# i2c_stm32.net
KiCad netlist of a schematic drawn in EAGLE
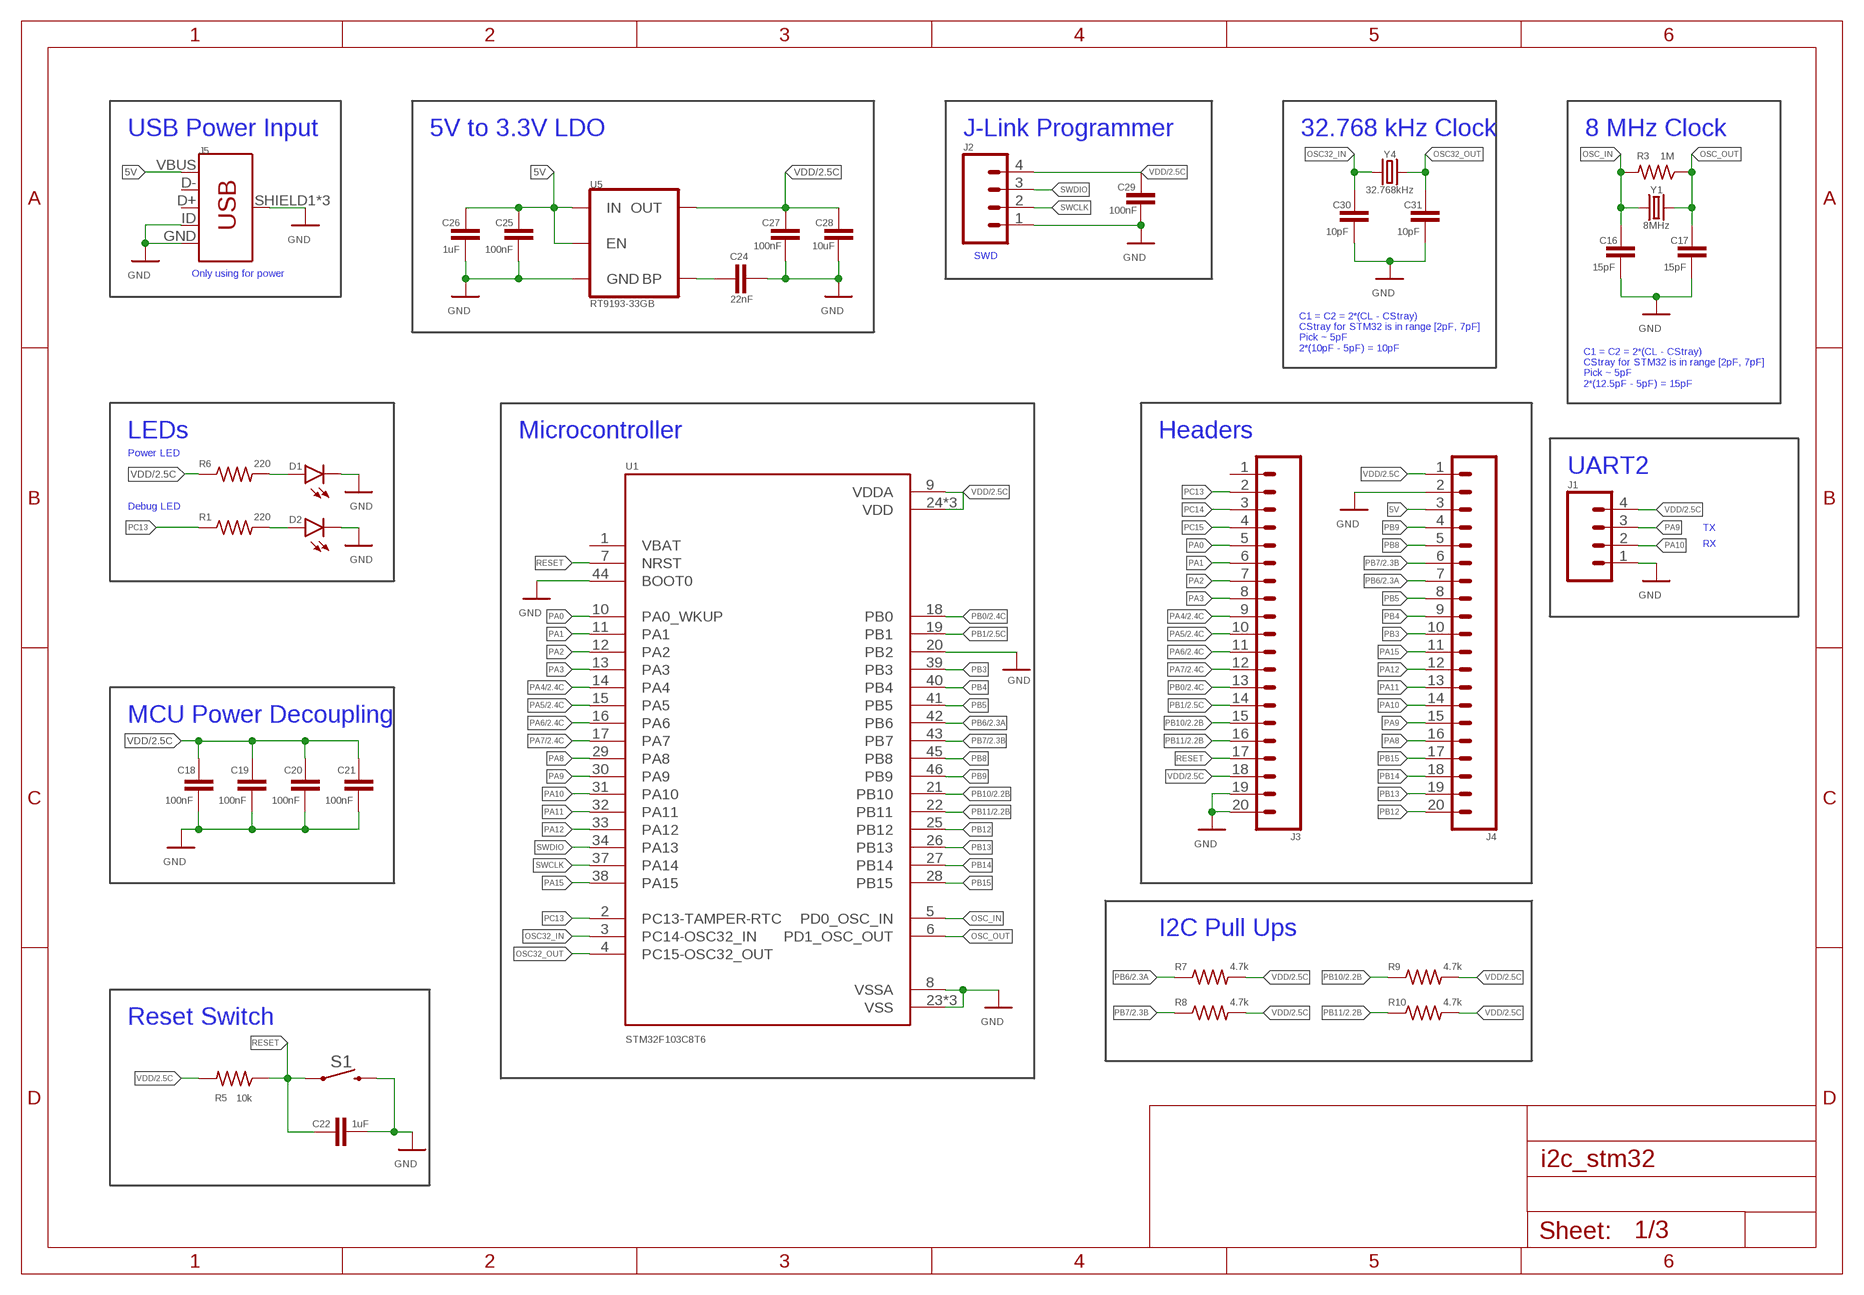
[diagram p0: schematic, sheet 1]
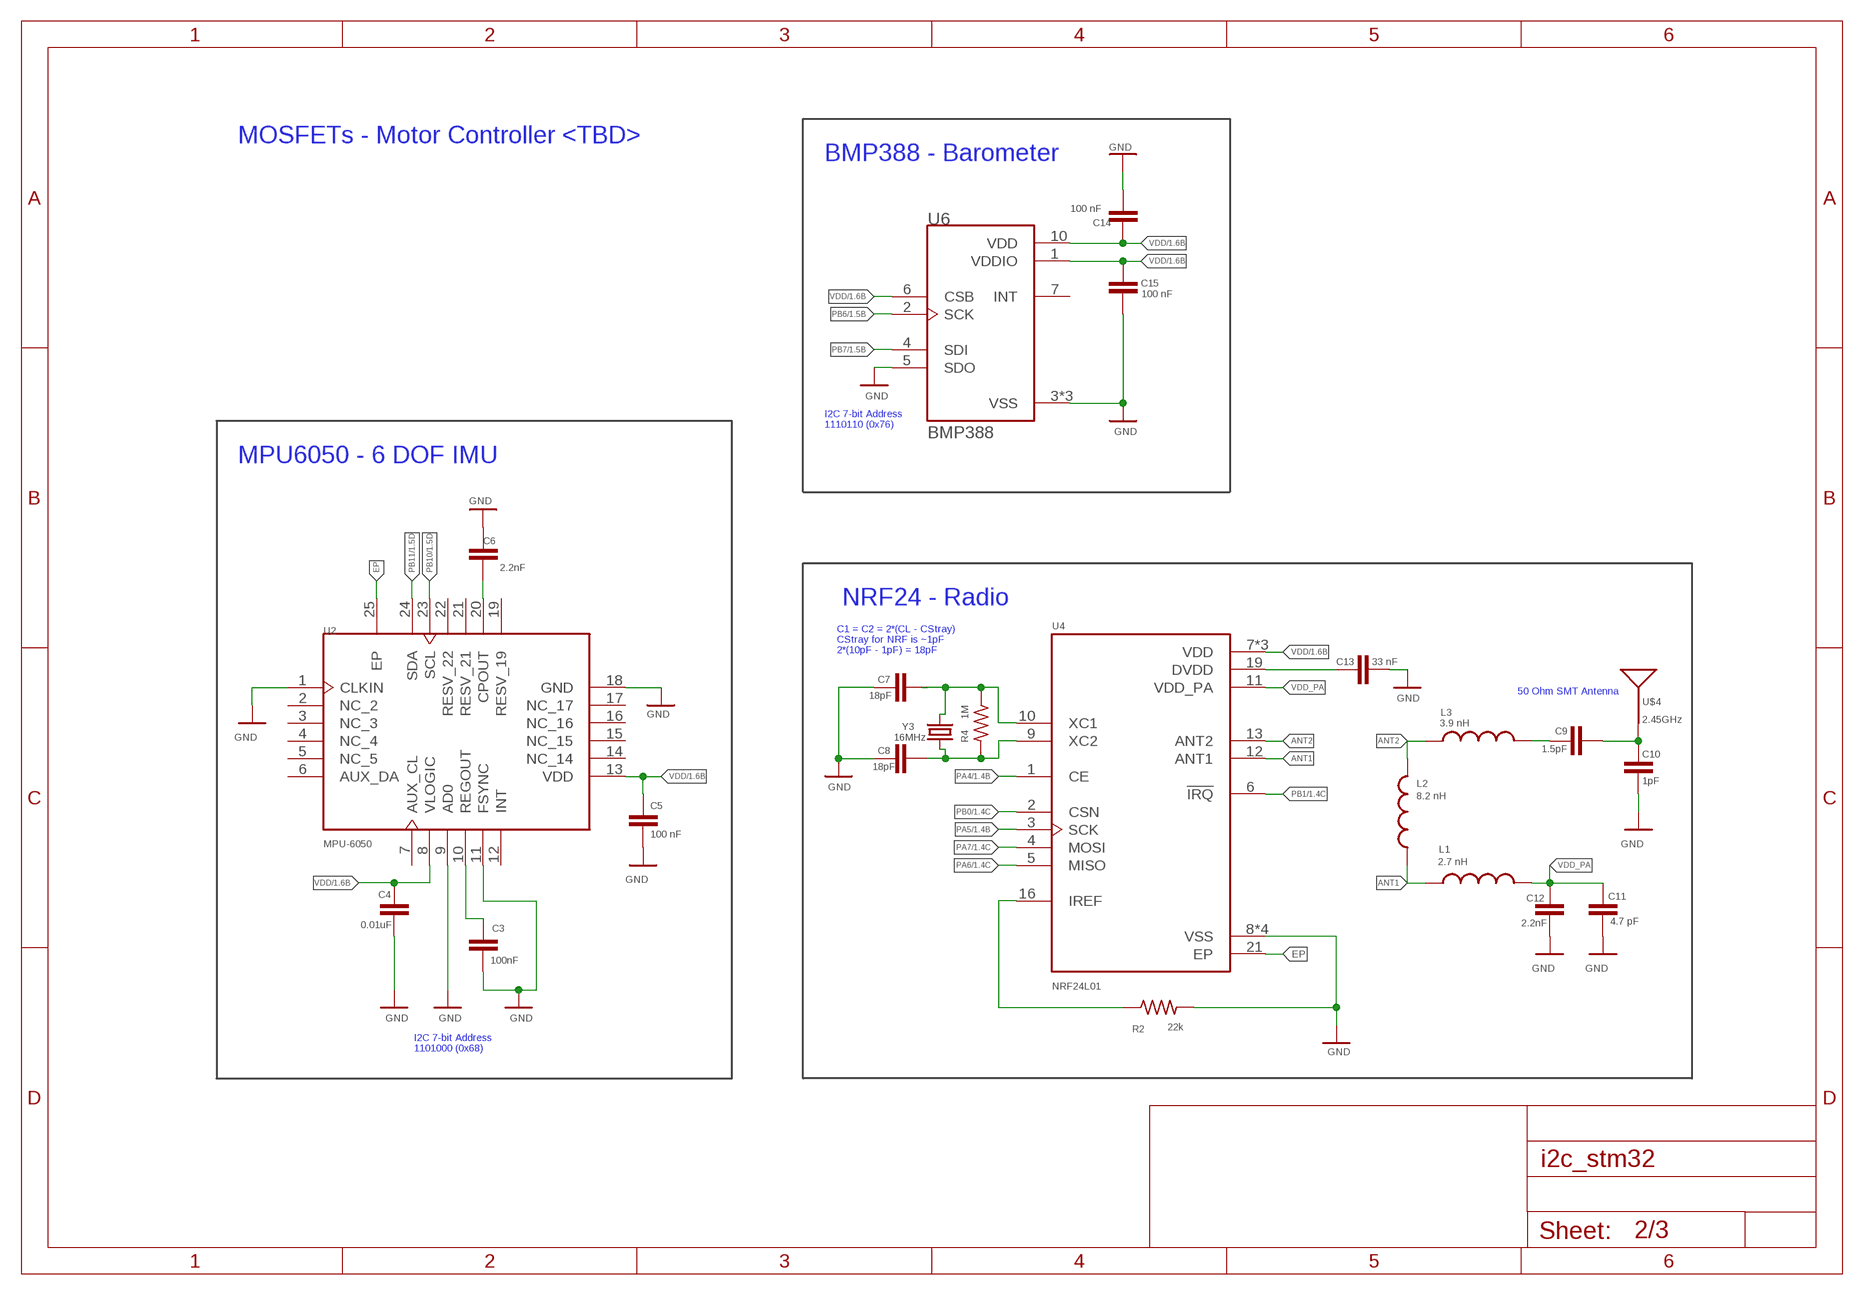
[diagram p1: schematic, sheet 2]
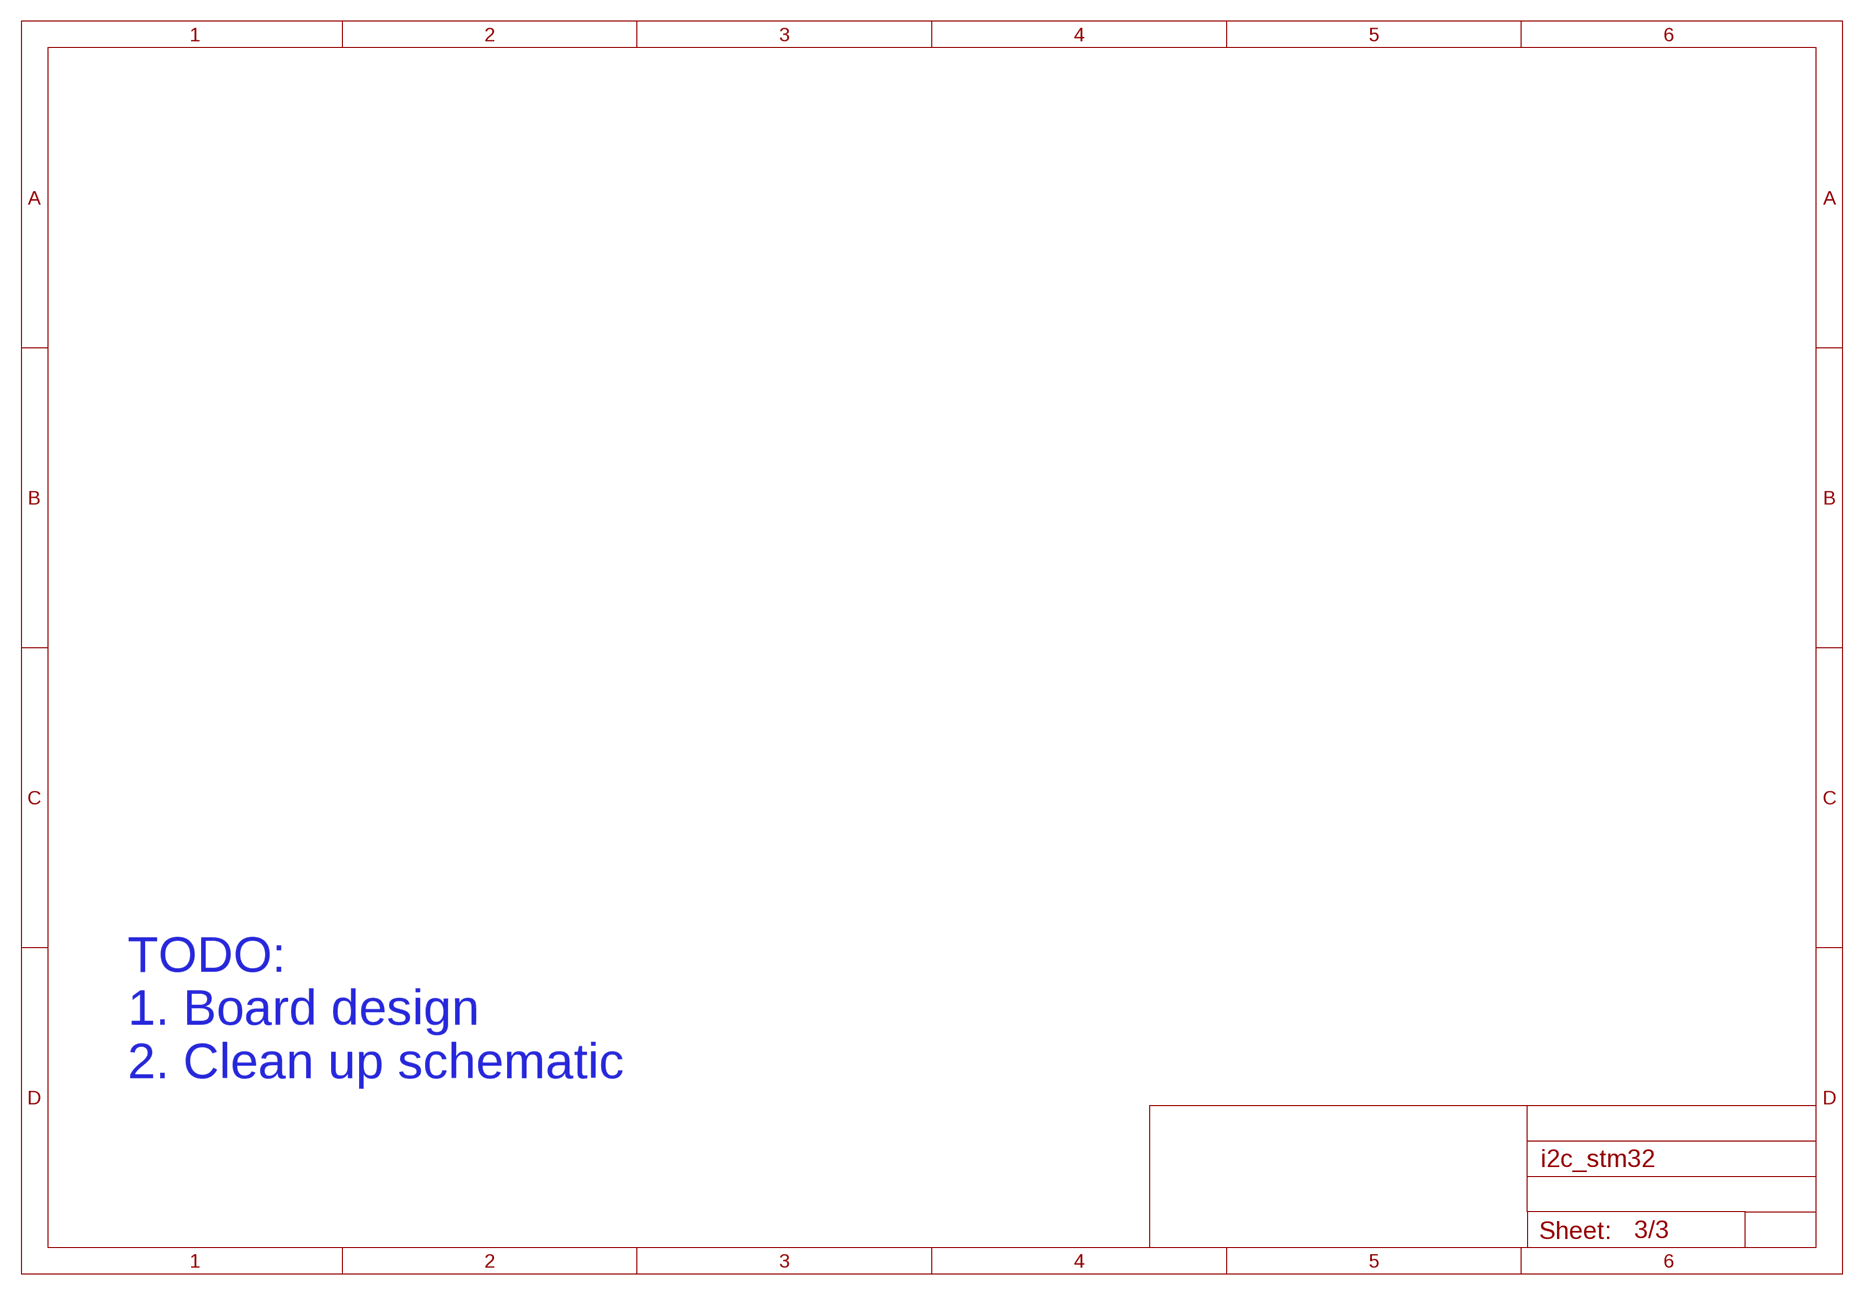
[diagram p2: schematic, sheet 3]

(export (version "E")
  (design (tool "Eeschema 10.0.6"))
  (components
    (comp (ref "C3")
      (value "100nF")
      (footprint "eagle-import:CAP_0603")
      (fields
        (field (name "DIGIKEY_PART_NUMBER") "399-7814-2-ND")
        (field (name "MANUFACTURER") "KEMET")
        (field (name "MPN") "C0603C100C5GACTU")
        (field (name "CREATED_BY") "PCBLayout.com")
      )
      (libsource (lib "eagle-import") (part "C0603C100C5GACTU"))
    )
    (comp (ref "C4")
      (value "0.01uF")
      (footprint "eagle-import:CAP_0603")
      (fields
        (field (name "DIGIKEY_PART_NUMBER") "399-7814-2-ND")
        (field (name "MANUFACTURER") "KEMET")
        (field (name "MPN") "C0603C100C5GACTU")
        (field (name "CREATED_BY") "PCBLayout.com")
      )
      (libsource (lib "eagle-import") (part "C0603C100C5GACTU"))
    )
    (comp (ref "C5")
      (value "100 nF")
      (footprint "eagle-import:CAP_0603")
      (fields
        (field (name "DIGIKEY_PART_NUMBER") "399-7814-2-ND")
        (field (name "MANUFACTURER") "KEMET")
        (field (name "MPN") "C0603C100C5GACTU")
        (field (name "CREATED_BY") "PCBLayout.com")
      )
      (libsource (lib "eagle-import") (part "C0603C100C5GACTU"))
    )
    (comp (ref "C6")
      (value "2.2nF")
      (footprint "eagle-import:CAP_0603")
      (fields
        (field (name "DIGIKEY_PART_NUMBER") "399-7814-2-ND")
        (field (name "MANUFACTURER") "KEMET")
        (field (name "MPN") "C0603C100C5GACTU")
        (field (name "CREATED_BY") "PCBLayout.com")
      )
      (libsource (lib "eagle-import") (part "C0603C100C5GACTU"))
    )
    (comp (ref "C7")
      (value "18pF")
      (footprint "eagle-import:CAP_0603")
      (fields
        (field (name "DIGIKEY_PART_NUMBER") "399-7814-2-ND")
        (field (name "MANUFACTURER") "KEMET")
        (field (name "MPN") "C0603C100C5GACTU")
        (field (name "CREATED_BY") "PCBLayout.com")
      )
      (libsource (lib "eagle-import") (part "C0603C100C5GACTU"))
    )
    (comp (ref "C8")
      (value "18pF")
      (footprint "eagle-import:CAP_0603")
      (fields
        (field (name "DIGIKEY_PART_NUMBER") "399-7814-2-ND")
        (field (name "MANUFACTURER") "KEMET")
        (field (name "MPN") "C0603C100C5GACTU")
        (field (name "CREATED_BY") "PCBLayout.com")
      )
      (libsource (lib "eagle-import") (part "C0603C100C5GACTU"))
    )
    (comp (ref "C9")
      (value "1.5pF")
      (footprint "eagle-import:CAP_0603")
      (fields
        (field (name "DIGIKEY_PART_NUMBER") "399-7814-2-ND")
        (field (name "MANUFACTURER") "KEMET")
        (field (name "MPN") "C0603C100C5GACTU")
        (field (name "CREATED_BY") "PCBLayout.com")
      )
      (libsource (lib "eagle-import") (part "C0603C100C5GACTU"))
    )
    (comp (ref "C10")
      (value "1pF")
      (footprint "eagle-import:CAP_0603")
      (fields
        (field (name "DIGIKEY_PART_NUMBER") "399-7814-2-ND")
        (field (name "MANUFACTURER") "KEMET")
        (field (name "MPN") "C0603C100C5GACTU")
        (field (name "CREATED_BY") "PCBLayout.com")
      )
      (libsource (lib "eagle-import") (part "C0603C100C5GACTU"))
    )
    (comp (ref "C11")
      (value "4.7 pF")
      (footprint "eagle-import:CAP_0603")
      (fields
        (field (name "DIGIKEY_PART_NUMBER") "399-7814-2-ND")
        (field (name "MANUFACTURER") "KEMET")
        (field (name "MPN") "C0603C100C5GACTU")
        (field (name "CREATED_BY") "PCBLayout.com")
      )
      (libsource (lib "eagle-import") (part "C0603C100C5GACTU"))
    )
    (comp (ref "C12")
      (value "2.2nF")
      (footprint "eagle-import:CAP_0603")
      (fields
        (field (name "DIGIKEY_PART_NUMBER") "399-7814-2-ND")
        (field (name "MANUFACTURER") "KEMET")
        (field (name "MPN") "C0603C100C5GACTU")
        (field (name "CREATED_BY") "PCBLayout.com")
      )
      (libsource (lib "eagle-import") (part "C0603C100C5GACTU"))
    )
    (comp (ref "C13")
      (value "33 nF")
      (footprint "eagle-import:CAP_0603")
      (fields
        (field (name "DIGIKEY_PART_NUMBER") "399-7814-2-ND")
        (field (name "MANUFACTURER") "KEMET")
        (field (name "MPN") "C0603C100C5GACTU")
        (field (name "CREATED_BY") "PCBLayout.com")
      )
      (libsource (lib "eagle-import") (part "C0603C100C5GACTU"))
    )
    (comp (ref "C14")
      (value "100 nF")
      (footprint "eagle-import:CAP_0603")
      (fields
        (field (name "DIGIKEY_PART_NUMBER") "399-7814-2-ND")
        (field (name "MANUFACTURER") "KEMET")
        (field (name "MPN") "C0603C100C5GACTU")
        (field (name "CREATED_BY") "PCBLayout.com")
      )
      (libsource (lib "eagle-import") (part "C0603C100C5GACTU"))
    )
    (comp (ref "C15")
      (value "100 nF")
      (footprint "eagle-import:CAP_0603")
      (fields
        (field (name "DIGIKEY_PART_NUMBER") "399-7814-2-ND")
        (field (name "MANUFACTURER") "KEMET")
        (field (name "MPN") "C0603C100C5GACTU")
        (field (name "CREATED_BY") "PCBLayout.com")
      )
      (libsource (lib "eagle-import") (part "C0603C100C5GACTU"))
    )
    (comp (ref "L1")
      (value "2.7 nH")
      (footprint "eagle-import:RESC0603_M")
      (libsource (lib "eagle-import") (part "INDUCTOR_0603_M"))
    )
    (comp (ref "L2")
      (value "8.2 nH")
      (footprint "eagle-import:RESC0603_M")
      (libsource (lib "eagle-import") (part "INDUCTOR_0603_M"))
    )
    (comp (ref "L3")
      (value "3.9 nH")
      (footprint "eagle-import:RESC0603_M")
      (libsource (lib "eagle-import") (part "INDUCTOR_0603_M"))
    )
    (comp (ref "R2")
      (value "22k")
      (footprint "eagle-import:RES_0603")
      (fields
        (field (name "DIGIKEY_PART_NUMBER") "311-0.0GRTR-ND")
        (field (name "MANUFACTURER") "Yageo")
        (field (name "MPN") "RC0603JR-070RL")
        (field (name "CREATED_BY") "PCBLayout.com")
      )
      (libsource (lib "eagle-import") (part "RC0603JR-070RL"))
    )
    (comp (ref "R4")
      (value "1M")
      (footprint "eagle-import:RES_0603")
      (fields
        (field (name "DIGIKEY_PART_NUMBER") "311-0.0GRTR-ND")
        (field (name "MANUFACTURER") "Yageo")
        (field (name "MPN") "RC0603JR-070RL")
        (field (name "CREATED_BY") "PCBLayout.com")
      )
      (libsource (lib "eagle-import") (part "RC0603JR-070RL"))
    )
    (comp (ref "U$4")
      (value "2.45GHz")
      (footprint "eagle-import:ANT-2.4GHZ-6.5X2.2MM")
      (libsource (lib "eagle-import") (part "ANTENNA2.4GHZ-6.5X2.2MM"))
    )
    (comp (ref "U2")
      (value "MPU-6050")
      (footprint "eagle-import:24-VFQFN")
      (fields
        (field (name "DIGIKEY_PART_NUMBER") "1428-1007-1-ND")
        (field (name "MANUFACTURER") "TDK InvenSense")
        (field (name "CREATED_BY") "PCBLayout.com")
      )
      (libsource (lib "eagle-import") (part "MPU-6050"))
    )
    (comp (ref "U4")
      (value "NRF24L01")
      (footprint "eagle-import:QFN50P400X400X95-21N")
      (fields (field (name "MF") "Nordic"))
      (libsource (lib "eagle-import") (part "NRF24L01"))
    )
    (comp (ref "U6")
      (value "BMP388")
      (footprint "eagle-import:PQFN50P200X200X80-10N")
      (fields (field (name "DIGI-KEY_PART_NUMBER") "828-1079-1-ND") (field (name "MF") "Bosch Sensortec"))
      (libsource (lib "eagle-import") (part "BMP388"))
    )
    (comp (ref "Y3")
      (value "16MHz")
      (footprint "eagle-import:CRYSTAL-SMD-5X3.2-4PAD")
      (libsource (lib "eagle-import") (part "CRYSTAL-16MHZSMD-5X3.2"))
    )
    (comp (ref "C16")
      (value "15pF")
      (footprint "eagle-import:CAP_0603")
      (fields
        (field (name "DIGIKEY_PART_NUMBER") "399-7814-2-ND")
        (field (name "MANUFACTURER") "KEMET")
        (field (name "MPN") "C0603C100C5GACTU")
        (field (name "CREATED_BY") "PCBLayout.com")
      )
      (libsource (lib "eagle-import") (part "C0603C100C5GACTU"))
    )
    (comp (ref "C17")
      (value "15pF")
      (footprint "eagle-import:CAP_0603")
      (fields
        (field (name "DIGIKEY_PART_NUMBER") "399-7814-2-ND")
        (field (name "MANUFACTURER") "KEMET")
        (field (name "MPN") "C0603C100C5GACTU")
        (field (name "CREATED_BY") "PCBLayout.com")
      )
      (libsource (lib "eagle-import") (part "C0603C100C5GACTU"))
    )
    (comp (ref "C18")
      (value "100nF")
      (footprint "eagle-import:CAP_0603")
      (fields
        (field (name "DIGIKEY_PART_NUMBER") "399-7814-2-ND")
        (field (name "MANUFACTURER") "KEMET")
        (field (name "MPN") "C0603C100C5GACTU")
        (field (name "CREATED_BY") "PCBLayout.com")
      )
      (libsource (lib "eagle-import") (part "C0603C100C5GACTU"))
    )
    (comp (ref "C19")
      (value "100nF")
      (footprint "eagle-import:CAP_0603")
      (fields
        (field (name "DIGIKEY_PART_NUMBER") "399-7814-2-ND")
        (field (name "MANUFACTURER") "KEMET")
        (field (name "MPN") "C0603C100C5GACTU")
        (field (name "CREATED_BY") "PCBLayout.com")
      )
      (libsource (lib "eagle-import") (part "C0603C100C5GACTU"))
    )
    (comp (ref "C20")
      (value "100nF")
      (footprint "eagle-import:CAP_0603")
      (fields
        (field (name "DIGIKEY_PART_NUMBER") "399-7814-2-ND")
        (field (name "MANUFACTURER") "KEMET")
        (field (name "MPN") "C0603C100C5GACTU")
        (field (name "CREATED_BY") "PCBLayout.com")
      )
      (libsource (lib "eagle-import") (part "C0603C100C5GACTU"))
    )
    (comp (ref "C21")
      (value "100nF")
      (footprint "eagle-import:CAP_0603")
      (fields
        (field (name "DIGIKEY_PART_NUMBER") "399-7814-2-ND")
        (field (name "MANUFACTURER") "KEMET")
        (field (name "MPN") "C0603C100C5GACTU")
        (field (name "CREATED_BY") "PCBLayout.com")
      )
      (libsource (lib "eagle-import") (part "C0603C100C5GACTU"))
    )
    (comp (ref "C22")
      (value "1uF")
      (footprint "eagle-import:CAP_0603")
      (fields
        (field (name "DIGIKEY_PART_NUMBER") "399-7814-2-ND")
        (field (name "MANUFACTURER") "KEMET")
        (field (name "MPN") "C0603C100C5GACTU")
        (field (name "CREATED_BY") "PCBLayout.com")
      )
      (libsource (lib "eagle-import") (part "C0603C100C5GACTU"))
    )
    (comp (ref "C24")
      (value "22nF")
      (footprint "eagle-import:CAP_0603")
      (fields
        (field (name "DIGIKEY_PART_NUMBER") "399-7814-2-ND")
        (field (name "MANUFACTURER") "KEMET")
        (field (name "MPN") "C0603C100C5GACTU")
        (field (name "CREATED_BY") "PCBLayout.com")
      )
      (libsource (lib "eagle-import") (part "C0603C100C5GACTU"))
    )
    (comp (ref "C25")
      (value "100nF")
      (footprint "eagle-import:CAP_0603")
      (fields
        (field (name "DIGIKEY_PART_NUMBER") "399-7814-2-ND")
        (field (name "MANUFACTURER") "KEMET")
        (field (name "MPN") "C0603C100C5GACTU")
        (field (name "CREATED_BY") "PCBLayout.com")
      )
      (libsource (lib "eagle-import") (part "C0603C100C5GACTU"))
    )
    (comp (ref "C26")
      (value "1uF")
      (footprint "eagle-import:CAP_0603")
      (fields
        (field (name "DIGIKEY_PART_NUMBER") "399-7814-2-ND")
        (field (name "MANUFACTURER") "KEMET")
        (field (name "MPN") "C0603C100C5GACTU")
        (field (name "CREATED_BY") "PCBLayout.com")
      )
      (libsource (lib "eagle-import") (part "C0603C100C5GACTU"))
    )
    (comp (ref "C27")
      (value "100nF")
      (footprint "eagle-import:CAP_0603")
      (fields
        (field (name "DIGIKEY_PART_NUMBER") "399-7814-2-ND")
        (field (name "MANUFACTURER") "KEMET")
        (field (name "MPN") "C0603C100C5GACTU")
        (field (name "CREATED_BY") "PCBLayout.com")
      )
      (libsource (lib "eagle-import") (part "C0603C100C5GACTU"))
    )
    (comp (ref "C28")
      (value "10uF")
      (footprint "eagle-import:CAP_0603")
      (fields
        (field (name "DIGIKEY_PART_NUMBER") "399-7814-2-ND")
        (field (name "MANUFACTURER") "KEMET")
        (field (name "MPN") "C0603C100C5GACTU")
        (field (name "CREATED_BY") "PCBLayout.com")
      )
      (libsource (lib "eagle-import") (part "C0603C100C5GACTU"))
    )
    (comp (ref "C29")
      (value "100nF")
      (footprint "eagle-import:CAP_0603")
      (fields
        (field (name "DIGIKEY_PART_NUMBER") "399-7814-2-ND")
        (field (name "MANUFACTURER") "KEMET")
        (field (name "MPN") "C0603C100C5GACTU")
        (field (name "CREATED_BY") "PCBLayout.com")
      )
      (libsource (lib "eagle-import") (part "C0603C100C5GACTU"))
    )
    (comp (ref "C30")
      (value "10pF")
      (footprint "eagle-import:CAP_0603")
      (fields
        (field (name "DIGIKEY_PART_NUMBER") "399-7814-2-ND")
        (field (name "MANUFACTURER") "KEMET")
        (field (name "MPN") "C0603C100C5GACTU")
        (field (name "CREATED_BY") "PCBLayout.com")
      )
      (libsource (lib "eagle-import") (part "C0603C100C5GACTU"))
    )
    (comp (ref "C31")
      (value "10pF")
      (footprint "eagle-import:CAP_0603")
      (fields
        (field (name "DIGIKEY_PART_NUMBER") "399-7814-2-ND")
        (field (name "MANUFACTURER") "KEMET")
        (field (name "MPN") "C0603C100C5GACTU")
        (field (name "CREATED_BY") "PCBLayout.com")
      )
      (libsource (lib "eagle-import") (part "C0603C100C5GACTU"))
    )
    (comp (ref "D1")
      (value "LED0603")
      (footprint "eagle-import:LED-0603")
      (libsource (lib "eagle-import") (part "LED0603"))
    )
    (comp (ref "D2")
      (value "LED0603")
      (footprint "eagle-import:LED-0603")
      (libsource (lib "eagle-import") (part "LED0603"))
    )
    (comp (ref "J1")
      (value "CONN_04")
      (footprint "eagle-import:1X04")
      (libsource (lib "eagle-import") (part "CONN_04"))
    )
    (comp (ref "J2")
      (value "CONN_04")
      (footprint "eagle-import:1X04")
      (libsource (lib "eagle-import") (part "CONN_04"))
    )
    (comp (ref "J3")
      (value "CONN_20")
      (footprint "eagle-import:1X20")
      (libsource (lib "eagle-import") (part "CONN_20"))
    )
    (comp (ref "J4")
      (value "CONN_20")
      (footprint "eagle-import:1X20")
      (libsource (lib "eagle-import") (part "CONN_20"))
    )
    (comp (ref "J5")
      (value "USB_MICRO-B_FEMALE-SMT")
      (footprint "eagle-import:USB-B-MICRO-SMD")
      (libsource (lib "eagle-import") (part "USB_MICRO-B_FEMALE-SMT"))
    )
    (comp (ref "R1")
      (value "220")
      (footprint "eagle-import:RES_0603")
      (fields
        (field (name "DIGIKEY_PART_NUMBER") "311-0.0GRTR-ND")
        (field (name "MANUFACTURER") "Yageo")
        (field (name "MPN") "RC0603JR-070RL")
        (field (name "CREATED_BY") "PCBLayout.com")
      )
      (libsource (lib "eagle-import") (part "RC0603JR-070RL"))
    )
    (comp (ref "R3")
      (value "1M")
      (footprint "eagle-import:RES_0603")
      (fields
        (field (name "DIGIKEY_PART_NUMBER") "311-0.0GRTR-ND")
        (field (name "MANUFACTURER") "Yageo")
        (field (name "MPN") "RC0603JR-070RL")
        (field (name "CREATED_BY") "PCBLayout.com")
      )
      (libsource (lib "eagle-import") (part "RC0603JR-070RL"))
    )
    (comp (ref "R5")
      (value "10k")
      (footprint "eagle-import:RES_0603")
      (fields
        (field (name "DIGIKEY_PART_NUMBER") "311-0.0GRTR-ND")
        (field (name "MANUFACTURER") "Yageo")
        (field (name "MPN") "RC0603JR-070RL")
        (field (name "CREATED_BY") "PCBLayout.com")
      )
      (libsource (lib "eagle-import") (part "RC0603JR-070RL"))
    )
    (comp (ref "R6")
      (value "220")
      (footprint "eagle-import:RES_0603")
      (fields
        (field (name "DIGIKEY_PART_NUMBER") "311-0.0GRTR-ND")
        (field (name "MANUFACTURER") "Yageo")
        (field (name "MPN") "RC0603JR-070RL")
        (field (name "CREATED_BY") "PCBLayout.com")
      )
      (libsource (lib "eagle-import") (part "RC0603JR-070RL"))
    )
    (comp (ref "R7")
      (value "4.7k")
      (footprint "eagle-import:RES_0603")
      (fields
        (field (name "DIGIKEY_PART_NUMBER") "311-0.0GRTR-ND")
        (field (name "MANUFACTURER") "Yageo")
        (field (name "MPN") "RC0603JR-070RL")
        (field (name "CREATED_BY") "PCBLayout.com")
      )
      (libsource (lib "eagle-import") (part "RC0603JR-070RL"))
    )
    (comp (ref "R8")
      (value "4.7k")
      (footprint "eagle-import:RES_0603")
      (fields
        (field (name "DIGIKEY_PART_NUMBER") "311-0.0GRTR-ND")
        (field (name "MANUFACTURER") "Yageo")
        (field (name "MPN") "RC0603JR-070RL")
        (field (name "CREATED_BY") "PCBLayout.com")
      )
      (libsource (lib "eagle-import") (part "RC0603JR-070RL"))
    )
    (comp (ref "R9")
      (value "4.7k")
      (footprint "eagle-import:RES_0603")
      (fields
        (field (name "DIGIKEY_PART_NUMBER") "311-0.0GRTR-ND")
        (field (name "MANUFACTURER") "Yageo")
        (field (name "MPN") "RC0603JR-070RL")
        (field (name "CREATED_BY") "PCBLayout.com")
      )
      (libsource (lib "eagle-import") (part "RC0603JR-070RL"))
    )
    (comp (ref "R10")
      (value "4.7k")
      (footprint "eagle-import:RES_0603")
      (fields
        (field (name "DIGIKEY_PART_NUMBER") "311-0.0GRTR-ND")
        (field (name "MANUFACTURER") "Yageo")
        (field (name "MPN") "RC0603JR-070RL")
        (field (name "CREATED_BY") "PCBLayout.com")
      )
      (libsource (lib "eagle-import") (part "RC0603JR-070RL"))
    )
    (comp (ref "S1")
      (value "MOMENTARY-SWITCH-SPST-PTH-6.0MM")
      (footprint "eagle-import:TACTILE_SWITCH_PTH_6.0MM")
      (libsource (lib "eagle-import") (part "MOMENTARY-SWITCH-SPST-PTH-6.0MM"))
    )
    (comp (ref "U1")
      (value "STM32F103C8T6")
      (footprint "eagle-import:QFP50P900X900X160-48N")
      (fields (field (name "MF") "STMicroelectronics") (field (name "SPICEPREFIX") "X"))
      (libsource (lib "eagle-import") (part "STM32F103C8T6"))
    )
    (comp (ref "U5")
      (value "RT9193-33GB")
      (footprint "eagle-import:SOT23-5")
      (libsource (lib "eagle-import") (part "V_REG_MIC5205ADJ"))
    )
    (comp (ref "Y1")
      (value "8MHz")
      (footprint "eagle-import:CRYSTAL-SMD-5X3.2-4PAD")
      (libsource (lib "eagle-import") (part "CRYSTAL-8MHZSMD-5X3.2"))
    )
    (comp (ref "Y4")
      (value "32.768kHz")
      (footprint "eagle-import:CRYSTAL-SMD-3.2X1.5MM")
      (libsource (lib "eagle-import") (part "CRYSTAL-32.768KHZSMD-3.2X1.5"))
    )
  )
  (nets
    (net (code "1") (name "5V") (class "Default")
      (node (ref "C25") (pin "2") (pinfunction "2_2") (pintype "passive"))
      (node (ref "C26") (pin "2") (pinfunction "2_2") (pintype "passive"))
      (node (ref "J4") (pin "3") (pinfunction "3_3") (pintype "passive"))
      (node (ref "J5") (pin "VBUS") (pinfunction "VBUS_VBUS") (pintype "power_in"))
      (node (ref "U5") (pin "1") (pinfunction "IN_1") (pintype "input"))
      (node (ref "U5") (pin "3") (pinfunction "EN_3") (pintype "input"))
    )
    (net (code "2") (name "ANT1") (class "Default")
      (node (ref "L1") (pin "1") (pinfunction "1_1") (pintype "passive"))
      (node (ref "L2") (pin "1") (pinfunction "1_1") (pintype "passive"))
      (node (ref "U4") (pin "12") (pinfunction "ANT1_12") (pintype "bidirectional"))
    )
    (net (code "3") (name "ANT2") (class "Default")
      (node (ref "L2") (pin "2") (pinfunction "2_2") (pintype "passive"))
      (node (ref "L3") (pin "1") (pinfunction "1_1") (pintype "passive"))
      (node (ref "U4") (pin "13") (pinfunction "ANT2_13") (pintype "bidirectional"))
    )
    (net (code "4") (name "EP") (class "Default")
      (node (ref "U2") (pin "25") (pinfunction "EP_25") (pintype "power_in"))
      (node (ref "U4") (pin "21") (pinfunction "EP_21") (pintype "power_in"))
    )
    (net (code "5") (name "GND") (class "Default")
      (node (ref "C10") (pin "1") (pinfunction "1_1") (pintype "passive"))
      (node (ref "C11") (pin "1") (pinfunction "1_1") (pintype "passive"))
      (node (ref "C12") (pin "1") (pinfunction "1_1") (pintype "passive"))
      (node (ref "C13") (pin "2") (pinfunction "2_2") (pintype "passive"))
      (node (ref "C14") (pin "2") (pinfunction "2_2") (pintype "passive"))
      (node (ref "C15") (pin "1") (pinfunction "1_1") (pintype "passive"))
      (node (ref "C16") (pin "2") (pinfunction "2_2") (pintype "passive"))
      (node (ref "C17") (pin "2") (pinfunction "2_2") (pintype "passive"))
      (node (ref "C18") (pin "2") (pinfunction "2_2") (pintype "passive"))
      (node (ref "C19") (pin "2") (pinfunction "2_2") (pintype "passive"))
      (node (ref "C20") (pin "2") (pinfunction "2_2") (pintype "passive"))
      (node (ref "C21") (pin "2") (pinfunction "2_2") (pintype "passive"))
      (node (ref "C22") (pin "2") (pinfunction "2_2") (pintype "passive"))
      (node (ref "C24") (pin "1") (pinfunction "1_1") (pintype "passive"))
      (node (ref "C25") (pin "1") (pinfunction "1_1") (pintype "passive"))
      (node (ref "C26") (pin "1") (pinfunction "1_1") (pintype "passive"))
      (node (ref "C27") (pin "2") (pinfunction "2_2") (pintype "passive"))
      (node (ref "C28") (pin "2") (pinfunction "2_2") (pintype "passive"))
      (node (ref "C29") (pin "2") (pinfunction "2_2") (pintype "passive"))
      (node (ref "C3") (pin "2") (pinfunction "2_2") (pintype "passive"))
      (node (ref "C30") (pin "2") (pinfunction "2_2") (pintype "passive"))
      (node (ref "C31") (pin "2") (pinfunction "2_2") (pintype "passive"))
      (node (ref "C4") (pin "2") (pinfunction "2_2") (pintype "passive"))
      (node (ref "C5") (pin "2") (pinfunction "2_2") (pintype "passive"))
      (node (ref "C6") (pin "2") (pinfunction "2_2") (pintype "passive"))
      (node (ref "C7") (pin "2") (pinfunction "2_2") (pintype "passive"))
      (node (ref "C8") (pin "2") (pinfunction "2_2") (pintype "passive"))
      (node (ref "D1") (pin "C") (pinfunction "C_C") (pintype "passive"))
      (node (ref "D2") (pin "C") (pinfunction "C_C") (pintype "passive"))
      (node (ref "J1") (pin "1") (pinfunction "1_1") (pintype "passive"))
      (node (ref "J2") (pin "1") (pinfunction "1_1") (pintype "passive"))
      (node (ref "J3") (pin "19") (pinfunction "19_19") (pintype "passive"))
      (node (ref "J3") (pin "20") (pinfunction "20_20") (pintype "passive"))
      (node (ref "J4") (pin "2") (pinfunction "2_2") (pintype "passive"))
      (node (ref "J5") (pin "GND") (pinfunction "GND_GND") (pintype "power_in"))
      (node (ref "J5") (pin "ID") (pinfunction "ID_ID") (pintype "bidirectional"))
      (node (ref "J5") (pin "SHIELD1") (pinfunction "SHIELD_SHIELD1") (pintype "bidirectional"))
      (node (ref "J5") (pin "SHIELD2") (pinfunction "SHIELD_SHIELD2") (pintype "bidirectional"))
      (node (ref "J5") (pin "SHIELD3") (pinfunction "SHIELD_SHIELD3") (pintype "bidirectional"))
      (node (ref "R2") (pin "2") (pinfunction "2_2") (pintype "passive"))
      (node (ref "S1") (pin "3") (pinfunction "2_3") (pintype "passive"))
      (node (ref "U1") (pin "20") (pinfunction "PB2_20") (pintype "bidirectional"))
      (node (ref "U1") (pin "23") (pinfunction "VSS_23") (pintype "power_in"))
      (node (ref "U1") (pin "35") (pinfunction "VSS_35") (pintype "power_in"))
      (node (ref "U1") (pin "44") (pinfunction "BOOT0_44") (pintype "input"))
      (node (ref "U1") (pin "47") (pinfunction "VSS_47") (pintype "power_in"))
      (node (ref "U1") (pin "8") (pinfunction "VSSA_8") (pintype "power_in"))
      (node (ref "U2") (pin "1") (pinfunction "CLKIN_1") (pintype "input"))
      (node (ref "U2") (pin "11") (pinfunction "FSYNC_11") (pintype "input"))
      (node (ref "U2") (pin "18") (pinfunction "GND_18") (pintype "power_in"))
      (node (ref "U2") (pin "9") (pinfunction "AD0_9") (pintype "bidirectional"))
      (node (ref "U4") (pin "14") (pinfunction "VSS_14") (pintype "power_in"))
      (node (ref "U4") (pin "17") (pinfunction "VSS_17") (pintype "power_in"))
      (node (ref "U4") (pin "20") (pinfunction "VSS_20") (pintype "power_in"))
      (node (ref "U4") (pin "8") (pinfunction "VSS_8") (pintype "power_in"))
      (node (ref "U5") (pin "2") (pinfunction "GND_2") (pintype "input"))
      (node (ref "U6") (pin "3") (pinfunction "VSS_3") (pintype "power_in"))
      (node (ref "U6") (pin "5") (pinfunction "SDO_5") (pintype "bidirectional"))
      (node (ref "U6") (pin "8") (pinfunction "VSS_8") (pintype "power_in"))
      (node (ref "U6") (pin "9") (pinfunction "VSS_9") (pintype "power_in"))
    )
    (net (code "6") (name "Net-(C9-Pad1)") (class "Default")
      (node (ref "C9") (pin "1") (pinfunction "1_1") (pintype "passive"))
      (node (ref "L3") (pin "2") (pinfunction "2_2") (pintype "passive"))
    )
    (net (code "7") (name "Net-(D1-PadA)") (class "Default")
      (node (ref "D1") (pin "A") (pinfunction "A_A") (pintype "passive"))
      (node (ref "R6") (pin "2") (pinfunction "2_2") (pintype "passive"))
    )
    (net (code "8") (name "Net-(D2-PadA)") (class "Default")
      (node (ref "D2") (pin "A") (pinfunction "A_A") (pintype "passive"))
      (node (ref "R1") (pin "2") (pinfunction "2_2") (pintype "passive"))
    )
    (net (code "9") (name "Net-(U$4-SIGNAL)") (class "Default")
      (node (ref "C10") (pin "2") (pinfunction "2_2") (pintype "passive"))
      (node (ref "C9") (pin "2") (pinfunction "2_2") (pintype "passive"))
      (node (ref "U$4") (pin "FEED") (pinfunction "SIGNAL_FEED") (pintype "bidirectional"))
    )
    (net (code "10") (name "Net-(U2-CPOUT)") (class "Default")
      (node (ref "C6") (pin "1") (pinfunction "1_1") (pintype "passive"))
      (node (ref "U2") (pin "20") (pinfunction "CPOUT_20") (pintype "output"))
    )
    (net (code "11") (name "Net-(U2-REGOUT)") (class "Default")
      (node (ref "C3") (pin "1") (pinfunction "1_1") (pintype "passive"))
      (node (ref "U2") (pin "10") (pinfunction "REGOUT_10") (pintype "passive"))
    )
    (net (code "12") (name "Net-(U4-DVDD)") (class "Default")
      (node (ref "C13") (pin "1") (pinfunction "1_1") (pintype "passive"))
      (node (ref "U4") (pin "19") (pinfunction "DVDD_19") (pintype "power_in"))
    )
    (net (code "13") (name "Net-(U4-IREF)") (class "Default")
      (node (ref "R2") (pin "1") (pinfunction "1_1") (pintype "passive"))
      (node (ref "U4") (pin "16") (pinfunction "IREF_16") (pintype "input"))
    )
    (net (code "14") (name "Net-(U4-XC1)") (class "Default")
      (node (ref "C7") (pin "1") (pinfunction "1_1") (pintype "passive"))
      (node (ref "R4") (pin "1") (pinfunction "1_1") (pintype "passive"))
      (node (ref "U4") (pin "10") (pinfunction "XC1_10") (pintype "input"))
      (node (ref "Y3") (pin "3") (pinfunction "2_3") (pintype "passive"))
    )
    (net (code "15") (name "Net-(U4-XC2)") (class "Default")
      (node (ref "C8") (pin "1") (pinfunction "1_1") (pintype "passive"))
      (node (ref "R4") (pin "2") (pinfunction "2_2") (pintype "passive"))
      (node (ref "U4") (pin "9") (pinfunction "XC2_9") (pintype "output"))
      (node (ref "Y3") (pin "1") (pinfunction "1_1") (pintype "passive"))
    )
    (net (code "16") (name "Net-(U5-BP)") (class "Default")
      (node (ref "C24") (pin "2") (pinfunction "2_2") (pintype "passive"))
      (node (ref "U5") (pin "4") (pinfunction "BP_4") (pintype "input"))
    )
    (net (code "17") (name "OSC32_IN") (class "Default")
      (node (ref "C30") (pin "1") (pinfunction "1_1") (pintype "passive"))
      (node (ref "U1") (pin "3") (pinfunction "PC14-OSC32_IN_3") (pintype "bidirectional"))
      (node (ref "Y4") (pin "P$1") (pinfunction "1_P$1") (pintype "passive"))
    )
    (net (code "18") (name "OSC32_OUT") (class "Default")
      (node (ref "C31") (pin "1") (pinfunction "1_1") (pintype "passive"))
      (node (ref "U1") (pin "4") (pinfunction "PC15-OSC32_OUT_4") (pintype "bidirectional"))
      (node (ref "Y4") (pin "P$2") (pinfunction "2_P$2") (pintype "passive"))
    )
    (net (code "19") (name "OSC_IN") (class "Default")
      (node (ref "C16") (pin "1") (pinfunction "1_1") (pintype "passive"))
      (node (ref "R3") (pin "2") (pinfunction "2_2") (pintype "passive"))
      (node (ref "U1") (pin "5") (pinfunction "PD0_OSC_IN_5") (pintype "bidirectional"))
      (node (ref "Y1") (pin "1") (pinfunction "1_1") (pintype "passive"))
    )
    (net (code "20") (name "OSC_OUT") (class "Default")
      (node (ref "C17") (pin "1") (pinfunction "1_1") (pintype "passive"))
      (node (ref "R3") (pin "1") (pinfunction "1_1") (pintype "passive"))
      (node (ref "U1") (pin "6") (pinfunction "PD1_OSC_OUT_6") (pintype "bidirectional"))
      (node (ref "Y1") (pin "3") (pinfunction "2_3") (pintype "passive"))
    )
    (net (code "21") (name "PA0") (class "Default")
      (node (ref "J3") (pin "5") (pinfunction "5_5") (pintype "passive"))
      (node (ref "U1") (pin "10") (pinfunction "PA0_WKUP_10") (pintype "bidirectional"))
    )
    (net (code "22") (name "PA1") (class "Default")
      (node (ref "J3") (pin "6") (pinfunction "6_6") (pintype "passive"))
      (node (ref "U1") (pin "11") (pinfunction "PA1_11") (pintype "bidirectional"))
    )
    (net (code "23") (name "PA2") (class "Default")
      (node (ref "J3") (pin "7") (pinfunction "7_7") (pintype "passive"))
      (node (ref "U1") (pin "12") (pinfunction "PA2_12") (pintype "bidirectional"))
    )
    (net (code "24") (name "PA3") (class "Default")
      (node (ref "J3") (pin "8") (pinfunction "8_8") (pintype "passive"))
      (node (ref "U1") (pin "13") (pinfunction "PA3_13") (pintype "bidirectional"))
    )
    (net (code "25") (name "PA4") (class "Default")
      (node (ref "J3") (pin "9") (pinfunction "9_9") (pintype "passive"))
      (node (ref "U1") (pin "14") (pinfunction "PA4_14") (pintype "bidirectional"))
      (node (ref "U4") (pin "1") (pinfunction "CE_1") (pintype "input"))
    )
    (net (code "26") (name "PA5") (class "Default")
      (node (ref "J3") (pin "10") (pinfunction "10_10") (pintype "passive"))
      (node (ref "U1") (pin "15") (pinfunction "PA5_15") (pintype "bidirectional"))
      (node (ref "U4") (pin "3") (pinfunction "SCK_3") (pintype "input"))
    )
    (net (code "27") (name "PA6") (class "Default")
      (node (ref "J3") (pin "11") (pinfunction "11_11") (pintype "passive"))
      (node (ref "U1") (pin "16") (pinfunction "PA6_16") (pintype "bidirectional"))
      (node (ref "U4") (pin "5") (pinfunction "MISO_5") (pintype "output"))
    )
    (net (code "28") (name "PA7") (class "Default")
      (node (ref "J3") (pin "12") (pinfunction "12_12") (pintype "passive"))
      (node (ref "U1") (pin "17") (pinfunction "PA7_17") (pintype "bidirectional"))
      (node (ref "U4") (pin "4") (pinfunction "MOSI_4") (pintype "input"))
    )
    (net (code "29") (name "PA8") (class "Default")
      (node (ref "J4") (pin "16") (pinfunction "16_16") (pintype "passive"))
      (node (ref "U1") (pin "29") (pinfunction "PA8_29") (pintype "bidirectional"))
    )
    (net (code "30") (name "PA9") (class "Default")
      (node (ref "J1") (pin "3") (pinfunction "3_3") (pintype "passive"))
      (node (ref "J4") (pin "15") (pinfunction "15_15") (pintype "passive"))
      (node (ref "U1") (pin "30") (pinfunction "PA9_30") (pintype "bidirectional"))
    )
    (net (code "31") (name "PA10") (class "Default")
      (node (ref "J1") (pin "2") (pinfunction "2_2") (pintype "passive"))
      (node (ref "J4") (pin "14") (pinfunction "14_14") (pintype "passive"))
      (node (ref "U1") (pin "31") (pinfunction "PA10_31") (pintype "bidirectional"))
    )
    (net (code "32") (name "PA11") (class "Default")
      (node (ref "J4") (pin "13") (pinfunction "13_13") (pintype "passive"))
      (node (ref "U1") (pin "32") (pinfunction "PA11_32") (pintype "bidirectional"))
    )
    (net (code "33") (name "PA12") (class "Default")
      (node (ref "J4") (pin "12") (pinfunction "12_12") (pintype "passive"))
      (node (ref "U1") (pin "33") (pinfunction "PA12_33") (pintype "bidirectional"))
    )
    (net (code "34") (name "PA15") (class "Default")
      (node (ref "J4") (pin "11") (pinfunction "11_11") (pintype "passive"))
      (node (ref "U1") (pin "38") (pinfunction "PA15_38") (pintype "bidirectional"))
    )
    (net (code "35") (name "PB0") (class "Default")
      (node (ref "J3") (pin "13") (pinfunction "13_13") (pintype "passive"))
      (node (ref "U1") (pin "18") (pinfunction "PB0_18") (pintype "bidirectional"))
      (node (ref "U4") (pin "2") (pinfunction "CSN_2") (pintype "input"))
    )
    (net (code "36") (name "PB1") (class "Default")
      (node (ref "J3") (pin "14") (pinfunction "14_14") (pintype "passive"))
      (node (ref "U1") (pin "19") (pinfunction "PB1_19") (pintype "bidirectional"))
      (node (ref "U4") (pin "6") (pinfunction "~{IRQ}_6") (pintype "output"))
    )
    (net (code "37") (name "PB3") (class "Default")
      (node (ref "J4") (pin "10") (pinfunction "10_10") (pintype "passive"))
      (node (ref "U1") (pin "39") (pinfunction "PB3_39") (pintype "bidirectional"))
    )
    (net (code "38") (name "PB4") (class "Default")
      (node (ref "J4") (pin "9") (pinfunction "9_9") (pintype "passive"))
      (node (ref "U1") (pin "40") (pinfunction "PB4_40") (pintype "bidirectional"))
    )
    (net (code "39") (name "PB5") (class "Default")
      (node (ref "J4") (pin "8") (pinfunction "8_8") (pintype "passive"))
      (node (ref "U1") (pin "41") (pinfunction "PB5_41") (pintype "bidirectional"))
    )
    (net (code "40") (name "PB6") (class "Default")
      (node (ref "J4") (pin "7") (pinfunction "7_7") (pintype "passive"))
      (node (ref "R7") (pin "1") (pinfunction "1_1") (pintype "passive"))
      (node (ref "U1") (pin "42") (pinfunction "PB6_42") (pintype "bidirectional"))
      (node (ref "U6") (pin "2") (pinfunction "SCK_2") (pintype "input"))
    )
    (net (code "41") (name "PB7") (class "Default")
      (node (ref "J4") (pin "6") (pinfunction "6_6") (pintype "passive"))
      (node (ref "R8") (pin "1") (pinfunction "1_1") (pintype "passive"))
      (node (ref "U1") (pin "43") (pinfunction "PB7_43") (pintype "bidirectional"))
      (node (ref "U6") (pin "4") (pinfunction "SDI_4") (pintype "bidirectional"))
    )
    (net (code "42") (name "PB8") (class "Default")
      (node (ref "J4") (pin "5") (pinfunction "5_5") (pintype "passive"))
      (node (ref "U1") (pin "45") (pinfunction "PB8_45") (pintype "bidirectional"))
    )
    (net (code "43") (name "PB9") (class "Default")
      (node (ref "J4") (pin "4") (pinfunction "4_4") (pintype "passive"))
      (node (ref "U1") (pin "46") (pinfunction "PB9_46") (pintype "bidirectional"))
    )
    (net (code "44") (name "PB10") (class "Default")
      (node (ref "J3") (pin "15") (pinfunction "15_15") (pintype "passive"))
      (node (ref "R9") (pin "1") (pinfunction "1_1") (pintype "passive"))
      (node (ref "U1") (pin "21") (pinfunction "PB10_21") (pintype "bidirectional"))
      (node (ref "U2") (pin "23") (pinfunction "SCL_23") (pintype "bidirectional"))
    )
    (net (code "45") (name "PB11") (class "Default")
      (node (ref "J3") (pin "16") (pinfunction "16_16") (pintype "passive"))
      (node (ref "R10") (pin "1") (pinfunction "1_1") (pintype "passive"))
      (node (ref "U1") (pin "22") (pinfunction "PB11_22") (pintype "bidirectional"))
      (node (ref "U2") (pin "24") (pinfunction "SDA_24") (pintype "bidirectional"))
    )
    (net (code "46") (name "PB12") (class "Default")
      (node (ref "J4") (pin "20") (pinfunction "20_20") (pintype "passive"))
      (node (ref "U1") (pin "25") (pinfunction "PB12_25") (pintype "bidirectional"))
    )
    (net (code "47") (name "PB13") (class "Default")
      (node (ref "J4") (pin "19") (pinfunction "19_19") (pintype "passive"))
      (node (ref "U1") (pin "26") (pinfunction "PB13_26") (pintype "bidirectional"))
    )
    (net (code "48") (name "PB14") (class "Default")
      (node (ref "J4") (pin "18") (pinfunction "18_18") (pintype "passive"))
      (node (ref "U1") (pin "27") (pinfunction "PB14_27") (pintype "bidirectional"))
    )
    (net (code "49") (name "PB15") (class "Default")
      (node (ref "J4") (pin "17") (pinfunction "17_17") (pintype "passive"))
      (node (ref "U1") (pin "28") (pinfunction "PB15_28") (pintype "bidirectional"))
    )
    (net (code "50") (name "PC13") (class "Default")
      (node (ref "J3") (pin "2") (pinfunction "2_2") (pintype "passive"))
      (node (ref "R1") (pin "1") (pinfunction "1_1") (pintype "passive"))
      (node (ref "U1") (pin "2") (pinfunction "PC13-TAMPER-RTC_2") (pintype "bidirectional"))
    )
    (net (code "51") (name "PC14") (class "Default")
      (node (ref "J3") (pin "3") (pinfunction "3_3") (pintype "passive"))
    )
    (net (code "52") (name "PC15") (class "Default")
      (node (ref "J3") (pin "4") (pinfunction "4_4") (pintype "passive"))
    )
    (net (code "53") (name "RESET") (class "Default")
      (node (ref "C22") (pin "1") (pinfunction "1_1") (pintype "passive"))
      (node (ref "J3") (pin "17") (pinfunction "17_17") (pintype "passive"))
      (node (ref "R5") (pin "1") (pinfunction "1_1") (pintype "passive"))
      (node (ref "S1") (pin "1") (pinfunction "1_1") (pintype "passive"))
      (node (ref "U1") (pin "7") (pinfunction "NRST_7") (pintype "input"))
    )
    (net (code "54") (name "SWCLK") (class "Default")
      (node (ref "J2") (pin "2") (pinfunction "2_2") (pintype "passive"))
      (node (ref "U1") (pin "37") (pinfunction "PA14_37") (pintype "bidirectional"))
    )
    (net (code "55") (name "SWDIO") (class "Default")
      (node (ref "J2") (pin "3") (pinfunction "3_3") (pintype "passive"))
      (node (ref "U1") (pin "34") (pinfunction "PA13_34") (pintype "bidirectional"))
    )
    (net (code "56") (name "VDD") (class "Default")
      (node (ref "C14") (pin "1") (pinfunction "1_1") (pintype "passive"))
      (node (ref "C15") (pin "2") (pinfunction "2_2") (pintype "passive"))
      (node (ref "C18") (pin "1") (pinfunction "1_1") (pintype "passive"))
      (node (ref "C19") (pin "1") (pinfunction "1_1") (pintype "passive"))
      (node (ref "C20") (pin "1") (pinfunction "1_1") (pintype "passive"))
      (node (ref "C21") (pin "1") (pinfunction "1_1") (pintype "passive"))
      (node (ref "C27") (pin "1") (pinfunction "1_1") (pintype "passive"))
      (node (ref "C28") (pin "1") (pinfunction "1_1") (pintype "passive"))
      (node (ref "C29") (pin "1") (pinfunction "1_1") (pintype "passive"))
      (node (ref "C4") (pin "1") (pinfunction "1_1") (pintype "passive"))
      (node (ref "C5") (pin "1") (pinfunction "1_1") (pintype "passive"))
      (node (ref "J1") (pin "4") (pinfunction "4_4") (pintype "passive"))
      (node (ref "J2") (pin "4") (pinfunction "4_4") (pintype "passive"))
      (node (ref "J3") (pin "18") (pinfunction "18_18") (pintype "passive"))
      (node (ref "J4") (pin "1") (pinfunction "1_1") (pintype "passive"))
      (node (ref "R10") (pin "2") (pinfunction "2_2") (pintype "passive"))
      (node (ref "R5") (pin "2") (pinfunction "2_2") (pintype "passive"))
      (node (ref "R6") (pin "1") (pinfunction "1_1") (pintype "passive"))
      (node (ref "R7") (pin "2") (pinfunction "2_2") (pintype "passive"))
      (node (ref "R8") (pin "2") (pinfunction "2_2") (pintype "passive"))
      (node (ref "R9") (pin "2") (pinfunction "2_2") (pintype "passive"))
      (node (ref "U1") (pin "24") (pinfunction "VDD_24") (pintype "power_in"))
      (node (ref "U1") (pin "36") (pinfunction "VDD_36") (pintype "power_in"))
      (node (ref "U1") (pin "48") (pinfunction "VDD_48") (pintype "power_in"))
      (node (ref "U1") (pin "9") (pinfunction "VDDA_9") (pintype "power_in"))
      (node (ref "U2") (pin "13") (pinfunction "VDD_13") (pintype "power_in"))
      (node (ref "U2") (pin "8") (pinfunction "VLOGIC_8") (pintype "power_in"))
      (node (ref "U4") (pin "15") (pinfunction "VDD_15") (pintype "power_in"))
      (node (ref "U4") (pin "18") (pinfunction "VDD_18") (pintype "power_in"))
      (node (ref "U4") (pin "7") (pinfunction "VDD_7") (pintype "power_in"))
      (node (ref "U5") (pin "5") (pinfunction "OUT_5") (pintype "passive"))
      (node (ref "U6") (pin "1") (pinfunction "VDDIO_1") (pintype "power_in"))
      (node (ref "U6") (pin "10") (pinfunction "VDD_10") (pintype "power_in"))
      (node (ref "U6") (pin "6") (pinfunction "CSB_6") (pintype "input"))
    )
    (net (code "57") (name "VDD_PA") (class "Default")
      (node (ref "C11") (pin "2") (pinfunction "2_2") (pintype "passive"))
      (node (ref "C12") (pin "2") (pinfunction "2_2") (pintype "passive"))
      (node (ref "L1") (pin "2") (pinfunction "2_2") (pintype "passive"))
      (node (ref "U4") (pin "11") (pinfunction "VDD_PA_11") (pintype "power_in"))
    )
    (net (code "58") (name "unconnected-(J3-Pad1)") (class "Default")
      (node (ref "J3") (pin "1") (pinfunction "1_1") (pintype "passive"))
    )
    (net (code "59") (name "unconnected-(J5-PadD+)") (class "Default")
      (node (ref "J5") (pin "D+") (pinfunction "D+_D+") (pintype "bidirectional"))
    )
    (net (code "60") (name "unconnected-(J5-PadD-)") (class "Default")
      (node (ref "J5") (pin "D-") (pinfunction "D-_D-") (pintype "bidirectional"))
    )
    (net (code "61") (name "unconnected-(U1-VBAT-Pad1)") (class "Default")
      (node (ref "U1") (pin "1") (pinfunction "VBAT_1") (pintype "bidirectional"))
    )
    (net (code "62") (name "unconnected-(U2-AUX_CL-Pad7)") (class "Default")
      (node (ref "U2") (pin "7") (pinfunction "AUX_CL_7") (pintype "bidirectional"))
    )
    (net (code "63") (name "unconnected-(U2-AUX_DA-Pad6)") (class "Default")
      (node (ref "U2") (pin "6") (pinfunction "AUX_DA_6") (pintype "bidirectional"))
    )
    (net (code "64") (name "unconnected-(U2-INT-Pad12)") (class "Default")
      (node (ref "U2") (pin "12") (pinfunction "INT_12") (pintype "output"))
    )
    (net (code "65") (name "unconnected-(U2-NC_2-Pad2)") (class "Default")
      (node (ref "U2") (pin "2") (pinfunction "NC_2_2") (pintype "passive"))
    )
    (net (code "66") (name "unconnected-(U2-NC_3-Pad3)") (class "Default")
      (node (ref "U2") (pin "3") (pinfunction "NC_3_3") (pintype "passive"))
    )
    (net (code "67") (name "unconnected-(U2-NC_4-Pad4)") (class "Default")
      (node (ref "U2") (pin "4") (pinfunction "NC_4_4") (pintype "passive"))
    )
    (net (code "68") (name "unconnected-(U2-NC_5-Pad5)") (class "Default")
      (node (ref "U2") (pin "5") (pinfunction "NC_5_5") (pintype "passive"))
    )
    (net (code "69") (name "unconnected-(U2-NC_14-Pad14)") (class "Default")
      (node (ref "U2") (pin "14") (pinfunction "NC_14_14") (pintype "passive"))
    )
    (net (code "70") (name "unconnected-(U2-NC_15-Pad15)") (class "Default")
      (node (ref "U2") (pin "15") (pinfunction "NC_15_15") (pintype "passive"))
    )
    (net (code "71") (name "unconnected-(U2-NC_16-Pad16)") (class "Default")
      (node (ref "U2") (pin "16") (pinfunction "NC_16_16") (pintype "passive"))
    )
    (net (code "72") (name "unconnected-(U2-NC_17-Pad17)") (class "Default")
      (node (ref "U2") (pin "17") (pinfunction "NC_17_17") (pintype "passive"))
    )
    (net (code "73") (name "unconnected-(U2-RESV_19-Pad19)") (class "Default")
      (node (ref "U2") (pin "19") (pinfunction "RESV_19_19") (pintype "passive"))
    )
    (net (code "74") (name "unconnected-(U2-RESV_21-Pad21)") (class "Default")
      (node (ref "U2") (pin "21") (pinfunction "RESV_21_21") (pintype "passive"))
    )
    (net (code "75") (name "unconnected-(U2-RESV_22-Pad22)") (class "Default")
      (node (ref "U2") (pin "22") (pinfunction "RESV_22_22") (pintype "passive"))
    )
    (net (code "76") (name "unconnected-(U6-INT-Pad7)") (class "Default")
      (node (ref "U6") (pin "7") (pinfunction "INT_7") (pintype "output"))
    )
  )
)
